# Lab2_Schem.net
KiCad netlist of a schematic drawn in EAGLE
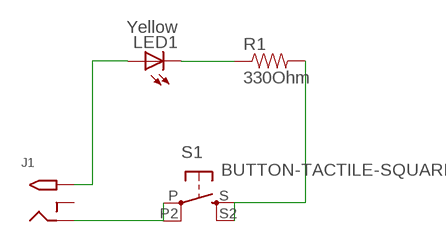
[diagram p0: schematic, sheet 1]

(export (version "E")
  (design (tool "Eeschema 10.0.6"))
  (components
    (comp (ref "J1")
      (value "2.1MMJACKTHM")
      (footprint "eagle-import:PJ-102A")
      (libsource (lib "eagle-import") (part "2.1MMJACKTHM"))
    )
    (comp (ref "LED1")
      (value "Yellow")
      (footprint "eagle-import:LED5MM")
      (libsource (lib "eagle-import") (part "LED5MM"))
    )
    (comp (ref "R1")
      (value "330Ohm")
      (footprint "eagle-import:AXIAL-0.3")
      (libsource (lib "eagle-import") (part "RESISTORAXIAL-0.3"))
    )
    (comp (ref "S1")
      (value "BUTTON-TACTILE-SQUARE")
      (footprint "eagle-import:BUTTON-TACTILE-SQUARE-ADAFRUIT1010")
      (libsource (lib "eagle-import") (part "BUTTON-TACTILE-SQUARE"))
    )
  )
  (nets
    (net (code "1") (name "Net-(J1-PadTIP)") (class "Default")
      (node (ref "J1") (pin "TIP") (pinfunction "TIP_TIP") (pintype "bidirectional"))
      (node (ref "LED1") (pin "A") (pinfunction "A_A") (pintype "passive"))
    )
    (net (code "2") (name "Net-(LED1-C)") (class "Default")
      (node (ref "LED1") (pin "K") (pinfunction "C_K") (pintype "passive"))
      (node (ref "R1") (pin "P$1") (pinfunction "1_P$1") (pintype "passive"))
    )
    (net (code "3") (name "Net-(R1-2)") (class "Default")
      (node (ref "R1") (pin "P$2") (pinfunction "2_P$2") (pintype "passive"))
      (node (ref "S1") (pin "S") (pinfunction "S_S") (pintype "passive"))
      (node (ref "S1") (pin "S2") (pinfunction "S1_S2") (pintype "passive"))
    )
    (net (code "4") (name "Net-(S1-P1)") (class "Default")
      (node (ref "J1") (pin "RING") (pinfunction "RING_RING") (pintype "bidirectional"))
      (node (ref "S1") (pin "P") (pinfunction "P_P") (pintype "passive"))
      (node (ref "S1") (pin "P2") (pinfunction "P1_P2") (pintype "passive"))
    )
    (net (code "5") (name "unconnected-(J1-PadRING_SW)") (class "Default")
      (node (ref "J1") (pin "RING_SW") (pinfunction "RING_SW_RING_SW") (pintype "bidirectional"))
    )
  )
)
